# PSDT_ADC_v1_0_0.net
KiCad netlist of a schematic drawn in Altium Designer
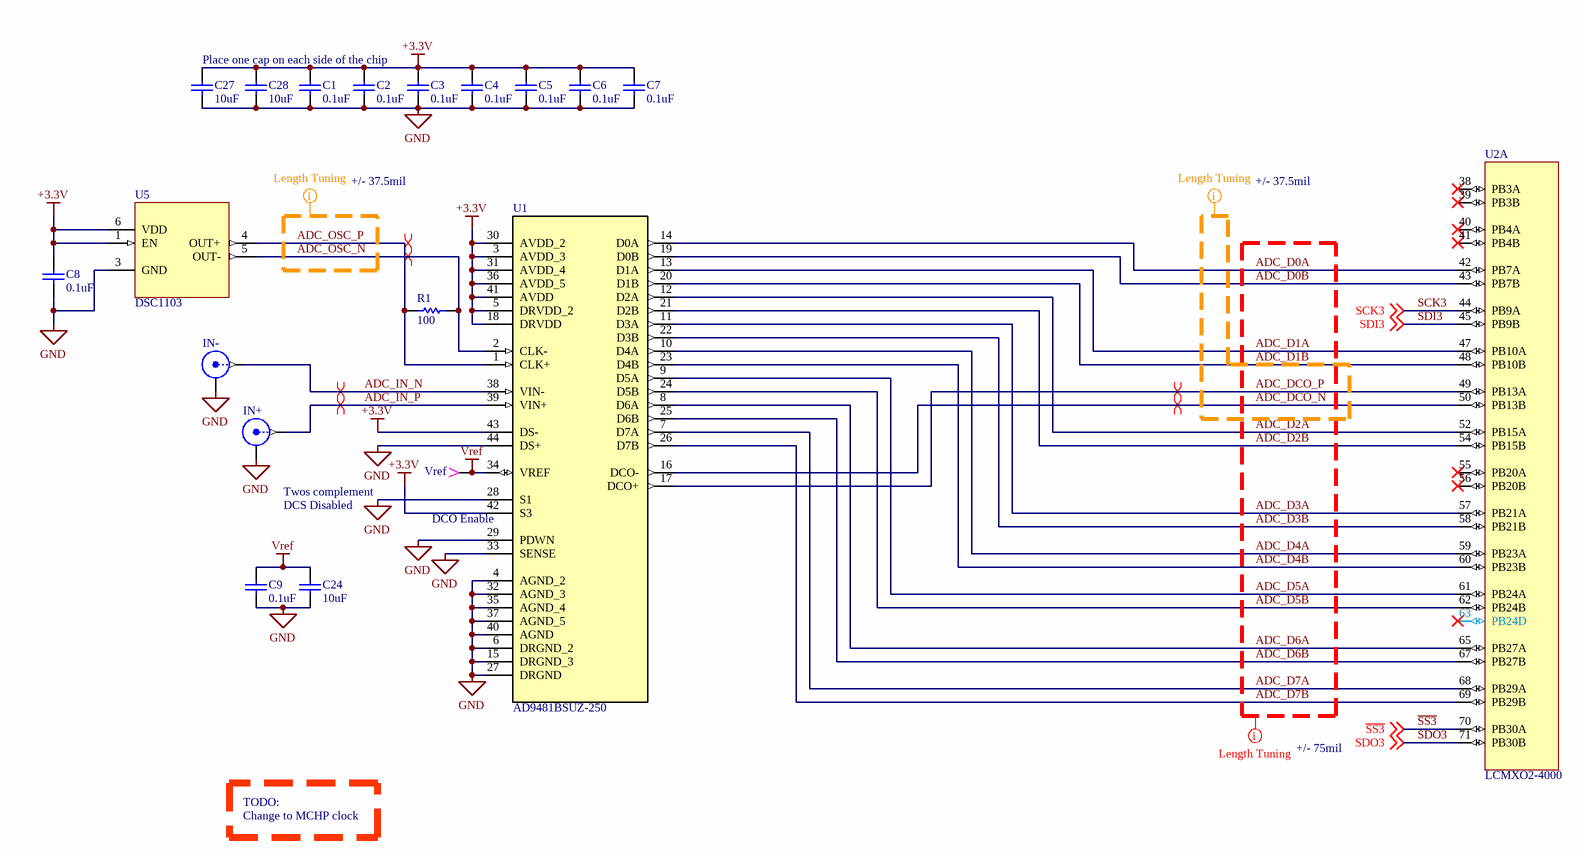
[diagram p0: PSDT ADC v1.0.0.SchDoc]

(export (version "E")
  (design (tool "Eeschema 10.0.6"))
  (components
    (comp (ref "C1")
      (value "0.1uF")
      (footprint "0402(1005)")
      (fields
        (field (name "MANF") "Samsung Electro-Mechanics")
        (field (name "TOLERANCE") "10")
        (field (name "VOLTAGE") "6.3")
        (field (name "MODIFIED BY") "jrowley")
        (field (name "APPROVED") "False")
      )
      (libsource (lib "MENG Database Library VPN") (part "Cap"))
    )
    (comp (ref "C2")
      (value "0.1uF")
      (footprint "0402(1005)")
      (fields
        (field (name "MANF") "Samsung Electro-Mechanics")
        (field (name "TOLERANCE") "10")
        (field (name "VOLTAGE") "6.3")
        (field (name "MODIFIED BY") "jrowley")
        (field (name "APPROVED") "False")
      )
      (libsource (lib "MENG Database Library VPN") (part "Cap"))
    )
    (comp (ref "C3")
      (value "0.1uF")
      (footprint "0402(1005)")
      (fields
        (field (name "MANF") "Samsung Electro-Mechanics")
        (field (name "TOLERANCE") "10")
        (field (name "VOLTAGE") "6.3")
        (field (name "MODIFIED BY") "jrowley")
        (field (name "APPROVED") "False")
      )
      (libsource (lib "MENG Database Library VPN") (part "Cap"))
    )
    (comp (ref "C4")
      (value "0.1uF")
      (footprint "0402(1005)")
      (fields
        (field (name "MANF") "Samsung Electro-Mechanics")
        (field (name "TOLERANCE") "10")
        (field (name "VOLTAGE") "6.3")
        (field (name "MODIFIED BY") "jrowley")
        (field (name "APPROVED") "False")
      )
      (libsource (lib "MENG Database Library VPN") (part "Cap"))
    )
    (comp (ref "C5")
      (value "0.1uF")
      (footprint "0402(1005)")
      (fields
        (field (name "MANF") "Samsung Electro-Mechanics")
        (field (name "TOLERANCE") "10")
        (field (name "VOLTAGE") "6.3")
        (field (name "MODIFIED BY") "jrowley")
        (field (name "APPROVED") "False")
      )
      (libsource (lib "MENG Database Library VPN") (part "Cap"))
    )
    (comp (ref "C6")
      (value "0.1uF")
      (footprint "0402(1005)")
      (fields
        (field (name "MANF") "Samsung Electro-Mechanics")
        (field (name "TOLERANCE") "10")
        (field (name "VOLTAGE") "6.3")
        (field (name "MODIFIED BY") "jrowley")
        (field (name "APPROVED") "False")
      )
      (libsource (lib "MENG Database Library VPN") (part "Cap"))
    )
    (comp (ref "C7")
      (value "0.1uF")
      (footprint "0402(1005)")
      (fields
        (field (name "MANF") "Samsung Electro-Mechanics")
        (field (name "TOLERANCE") "10")
        (field (name "VOLTAGE") "6.3")
        (field (name "MODIFIED BY") "jrowley")
        (field (name "APPROVED") "False")
      )
      (libsource (lib "MENG Database Library VPN") (part "Cap"))
    )
    (comp (ref "C8")
      (value "0.1uF")
      (footprint "0402(1005)")
      (fields
        (field (name "MANF") "Samsung Electro-Mechanics")
        (field (name "TOLERANCE") "10")
        (field (name "VOLTAGE") "6.3")
        (field (name "MODIFIED BY") "jrowley")
        (field (name "APPROVED") "False")
      )
      (libsource (lib "MENG Database Library VPN") (part "Cap"))
    )
    (comp (ref "C9")
      (value "0.1uF")
      (footprint "0402(1005)")
      (fields
        (field (name "MANF") "Samsung Electro-Mechanics")
        (field (name "TOLERANCE") "10")
        (field (name "VOLTAGE") "6.3")
        (field (name "MODIFIED BY") "jrowley")
        (field (name "APPROVED") "False")
      )
      (libsource (lib "MENG Database Library VPN") (part "Cap"))
    )
    (comp (ref "C24")
      (value "10uF")
      (footprint "0603(1608)")
      (fields
        (field (name "MANF") "Samsung Electro-Mechanics")
        (field (name "TOLERANCE") "20")
        (field (name "VOLTAGE") "25")
        (field (name "MODIFIED BY") "sotterbacher")
        (field (name "APPROVED") "True")
      )
      (libsource (lib "MENG Database Library VPN") (part "Cap"))
    )
    (comp (ref "C27")
      (value "10uF")
      (footprint "0603(1608)")
      (fields
        (field (name "MANF") "Samsung Electro-Mechanics")
        (field (name "TOLERANCE") "20")
        (field (name "VOLTAGE") "25")
        (field (name "MODIFIED BY") "sotterbacher")
        (field (name "APPROVED") "True")
      )
      (libsource (lib "MENG Database Library VPN") (part "Cap"))
    )
    (comp (ref "C28")
      (value "10uF")
      (footprint "0603(1608)")
      (fields
        (field (name "MANF") "Samsung Electro-Mechanics")
        (field (name "TOLERANCE") "20")
        (field (name "VOLTAGE") "25")
        (field (name "MODIFIED BY") "sotterbacher")
        (field (name "APPROVED") "True")
      )
      (libsource (lib "MENG Database Library VPN") (part "Cap"))
    )
    (comp (ref "IN+")
      (value "SMA")
      (footprint "TE SMA Stright")
      (fields
        (field (name "MANF") "TE Connectivity")
        (field (name "MODIFIED BY") "rlaity")
        (field (name "APPROVED") "True")
      )
      (libsource (lib "MENG Database Library VPN") (part "BNC"))
    )
    (comp (ref "IN-")
      (value "SMA")
      (footprint "TE SMA Stright")
      (fields
        (field (name "MANF") "TE Connectivity")
        (field (name "MODIFIED BY") "rlaity")
        (field (name "APPROVED") "True")
      )
      (libsource (lib "MENG Database Library VPN") (part "BNC"))
    )
    (comp (ref "R1")
      (value "100")
      (footprint "0402(1005)")
      (fields
        (field (name "MANF") "Yageo")
        (field (name "TOLERANCE") "1")
        (field (name "POWER") "0.0625")
        (field (name "MODIFIED BY") "jrowley")
        (field (name "APPROVED") "False")
      )
      (libsource (lib "MENG Database Library VPN") (part "Res1"))
    )
    (comp (ref "U1")
      (value "AD9481BSUZ-250")
      (footprint "QFP80P1200X1200X120-44N")
      (description "Single ADC Pipelined 250Msps 8-bit Parallel/LVDS 44-Pin TQFP Tray")
      (fields (field (name "MANF") "Analog Devices Inc."))
      (libsource (lib "PS") (part "AD9481BSUZ-250"))
    )
    (comp (ref "U2")
      (value "LCMXO2-4000")
      (footprint "UL_TQFP144")
      (fields (field (name "MANF") "Lattice Semiconductor Corporation"))
      (libsource (lib "PS") (part "MachXO2-4000-TG144"))
    )
    (comp (ref "U5")
      (value "DSC1103")
      (footprint "MCHP_H5A")
      (fields (field (name "MANF") "Microchip Technology"))
      (libsource (lib "PS v1.0") (part "DSC1103"))
    )
    (comp (ref "Vref")
      (value "TP")
      (footprint "TESTPOINT024")
      (fields
        (field (name "MANF") "Keystone Electronics")
        (field (name "APPROVED") "True")
        (field (name "MODIFIED BY") "sotterbacher")
      )
      (libsource (lib "MENG Database Library VPN") (part "TP"))
    )
  )
  (nets
    (net (code "1") (name "+3.3V") (class "Default")
      (node (ref "C1") (pin "2") (pinfunction "2_2") (pintype "passive"))
      (node (ref "C2") (pin "2") (pinfunction "2_2") (pintype "passive"))
      (node (ref "C27") (pin "2") (pinfunction "2_2") (pintype "passive"))
      (node (ref "C28") (pin "2") (pinfunction "2_2") (pintype "passive"))
      (node (ref "C3") (pin "2") (pinfunction "2_2") (pintype "passive"))
      (node (ref "C4") (pin "2") (pinfunction "2_2") (pintype "passive"))
      (node (ref "C5") (pin "2") (pinfunction "2_2") (pintype "passive"))
      (node (ref "C6") (pin "2") (pinfunction "2_2") (pintype "passive"))
      (node (ref "C7") (pin "2") (pinfunction "2_2") (pintype "passive"))
      (node (ref "C8") (pin "2") (pinfunction "2_2") (pintype "passive"))
      (node (ref "U1") (pin "18") (pinfunction "DRVDD_18") (pintype "power_in"))
      (node (ref "U1") (pin "3") (pinfunction "AVDD_3_3") (pintype "power_in"))
      (node (ref "U1") (pin "30") (pinfunction "AVDD_2_30") (pintype "power_in"))
      (node (ref "U1") (pin "31") (pinfunction "AVDD_4_31") (pintype "power_in"))
      (node (ref "U1") (pin "36") (pinfunction "AVDD_5_36") (pintype "power_in"))
      (node (ref "U1") (pin "41") (pinfunction "AVDD_41") (pintype "power_in"))
      (node (ref "U1") (pin "42") (pinfunction "S3_42") (pintype "passive"))
      (node (ref "U1") (pin "43") (pinfunction "DS-_43") (pintype "passive"))
      (node (ref "U1") (pin "5") (pinfunction "DRVDD_2_5") (pintype "power_in"))
      (node (ref "U5") (pin "1") (pinfunction "EN_1") (pintype "input"))
      (node (ref "U5") (pin "6") (pinfunction "VDD_6") (pintype "power_in"))
    )
    (net (code "2") (name "/ADC_D0A") (class "Default")
      (node (ref "U1") (pin "14") (pinfunction "D0A_14") (pintype "output"))
      (node (ref "U2") (pin "42") (pinfunction "PB7A_42") (pintype "bidirectional"))
    )
    (net (code "3") (name "/ADC_D0B") (class "Default")
      (node (ref "U1") (pin "19") (pinfunction "D0B_19") (pintype "output"))
      (node (ref "U2") (pin "43") (pinfunction "PB7B_43") (pintype "bidirectional"))
    )
    (net (code "4") (name "/ADC_D1A") (class "Default")
      (node (ref "U1") (pin "13") (pinfunction "D1A_13") (pintype "output"))
      (node (ref "U2") (pin "47") (pinfunction "PB10A_47") (pintype "bidirectional"))
    )
    (net (code "5") (name "/ADC_D1B") (class "Default")
      (node (ref "U1") (pin "20") (pinfunction "D1B_20") (pintype "output"))
      (node (ref "U2") (pin "48") (pinfunction "PB10B_48") (pintype "bidirectional"))
    )
    (net (code "6") (name "/ADC_D2A") (class "Default")
      (node (ref "U1") (pin "12") (pinfunction "D2A_12") (pintype "output"))
      (node (ref "U2") (pin "52") (pinfunction "PB15A_52") (pintype "bidirectional"))
    )
    (net (code "7") (name "/ADC_D2B") (class "Default")
      (node (ref "U1") (pin "21") (pinfunction "D2B_21") (pintype "output"))
      (node (ref "U2") (pin "54") (pinfunction "PB15B_54") (pintype "bidirectional"))
    )
    (net (code "8") (name "/ADC_D3A") (class "Default")
      (node (ref "U1") (pin "11") (pinfunction "D3A_11") (pintype "output"))
      (node (ref "U2") (pin "57") (pinfunction "PB21A_57") (pintype "bidirectional"))
    )
    (net (code "9") (name "/ADC_D3B") (class "Default")
      (node (ref "U1") (pin "22") (pinfunction "D3B_22") (pintype "output"))
      (node (ref "U2") (pin "58") (pinfunction "PB21B_58") (pintype "bidirectional"))
    )
    (net (code "10") (name "/ADC_D4A") (class "Default")
      (node (ref "U1") (pin "10") (pinfunction "D4A_10") (pintype "output"))
      (node (ref "U2") (pin "59") (pinfunction "PB23A_59") (pintype "bidirectional"))
    )
    (net (code "11") (name "/ADC_D4B") (class "Default")
      (node (ref "U1") (pin "23") (pinfunction "D4B_23") (pintype "output"))
      (node (ref "U2") (pin "60") (pinfunction "PB23B_60") (pintype "bidirectional"))
    )
    (net (code "12") (name "/ADC_D5A") (class "Default")
      (node (ref "U1") (pin "9") (pinfunction "D5A_9") (pintype "output"))
      (node (ref "U2") (pin "61") (pinfunction "PB24A_61") (pintype "bidirectional"))
    )
    (net (code "13") (name "/ADC_D5B") (class "Default")
      (node (ref "U1") (pin "24") (pinfunction "D5B_24") (pintype "output"))
      (node (ref "U2") (pin "62") (pinfunction "PB24B_62") (pintype "bidirectional"))
    )
    (net (code "14") (name "/ADC_D6A") (class "Default")
      (node (ref "U1") (pin "8") (pinfunction "D6A_8") (pintype "output"))
      (node (ref "U2") (pin "65") (pinfunction "PB27A_65") (pintype "bidirectional"))
    )
    (net (code "15") (name "/ADC_D6B") (class "Default")
      (node (ref "U1") (pin "25") (pinfunction "D6B_25") (pintype "output"))
      (node (ref "U2") (pin "67") (pinfunction "PB27B_67") (pintype "bidirectional"))
    )
    (net (code "16") (name "/ADC_D7A") (class "Default")
      (node (ref "U1") (pin "7") (pinfunction "D7A_7") (pintype "output"))
      (node (ref "U2") (pin "68") (pinfunction "PB29A_68") (pintype "bidirectional"))
    )
    (net (code "17") (name "/ADC_D7B") (class "Default")
      (node (ref "U1") (pin "26") (pinfunction "D7B_26") (pintype "output"))
      (node (ref "U2") (pin "69") (pinfunction "PB29B_69") (pintype "bidirectional"))
    )
    (net (code "18") (name "/ADC_DCO_N") (class "Default")
      (node (ref "U1") (pin "16") (pinfunction "DCO-_16") (pintype "output"))
      (node (ref "U2") (pin "50") (pinfunction "PB13B_50") (pintype "bidirectional"))
    )
    (net (code "19") (name "/ADC_DCO_P") (class "Default")
      (node (ref "U1") (pin "17") (pinfunction "DCO+_17") (pintype "output"))
      (node (ref "U2") (pin "49") (pinfunction "PB13A_49") (pintype "bidirectional"))
    )
    (net (code "20") (name "/ADC_IN_N") (class "Default")
      (node (ref "IN-") (pin "1") (pinfunction "X_1") (pintype "output"))
      (node (ref "U1") (pin "38") (pinfunction "VIN-_38") (pintype "input"))
    )
    (net (code "21") (name "/ADC_IN_P") (class "Default")
      (node (ref "IN+") (pin "1") (pinfunction "X_1") (pintype "output"))
      (node (ref "U1") (pin "39") (pinfunction "VIN+_39") (pintype "input"))
    )
    (net (code "22") (name "/ADC_OSC_N") (class "Default")
      (node (ref "R1") (pin "2") (pinfunction "2_2") (pintype "passive"))
      (node (ref "U1") (pin "2") (pinfunction "CLK-_2") (pintype "input"))
      (node (ref "U5") (pin "5") (pinfunction "OUT-_5") (pintype "output"))
    )
    (net (code "23") (name "/ADC_OSC_P") (class "Default")
      (node (ref "R1") (pin "1") (pinfunction "1_1") (pintype "passive"))
      (node (ref "U1") (pin "1") (pinfunction "CLK+_1") (pintype "input"))
      (node (ref "U5") (pin "4") (pinfunction "OUT+_4") (pintype "output"))
    )
    (net (code "24") (name "GND") (class "Default")
      (node (ref "C1") (pin "1") (pinfunction "1_1") (pintype "passive"))
      (node (ref "C2") (pin "1") (pinfunction "1_1") (pintype "passive"))
      (node (ref "C24") (pin "1") (pinfunction "1_1") (pintype "passive"))
      (node (ref "C27") (pin "1") (pinfunction "1_1") (pintype "passive"))
      (node (ref "C28") (pin "1") (pinfunction "1_1") (pintype "passive"))
      (node (ref "C3") (pin "1") (pinfunction "1_1") (pintype "passive"))
      (node (ref "C4") (pin "1") (pinfunction "1_1") (pintype "passive"))
      (node (ref "C5") (pin "1") (pinfunction "1_1") (pintype "passive"))
      (node (ref "C6") (pin "1") (pinfunction "1_1") (pintype "passive"))
      (node (ref "C7") (pin "1") (pinfunction "1_1") (pintype "passive"))
      (node (ref "C8") (pin "1") (pinfunction "1_1") (pintype "passive"))
      (node (ref "C9") (pin "1") (pinfunction "1_1") (pintype "passive"))
      (node (ref "IN+") (pin "2") (pinfunction "Y_2") (pintype "power_in"))
      (node (ref "IN-") (pin "2") (pinfunction "Y_2") (pintype "power_in"))
      (node (ref "U1") (pin "15") (pinfunction "DRGND_3_15") (pintype "passive"))
      (node (ref "U1") (pin "27") (pinfunction "DRGND_27") (pintype "passive"))
      (node (ref "U1") (pin "28") (pinfunction "S1_28") (pintype "passive"))
      (node (ref "U1") (pin "29") (pinfunction "PDWN_29") (pintype "passive"))
      (node (ref "U1") (pin "32") (pinfunction "AGND_3_32") (pintype "passive"))
      (node (ref "U1") (pin "33") (pinfunction "SENSE_33") (pintype "passive"))
      (node (ref "U1") (pin "35") (pinfunction "AGND_4_35") (pintype "passive"))
      (node (ref "U1") (pin "37") (pinfunction "AGND_5_37") (pintype "passive"))
      (node (ref "U1") (pin "4") (pinfunction "AGND_2_4") (pintype "passive"))
      (node (ref "U1") (pin "40") (pinfunction "AGND_40") (pintype "passive"))
      (node (ref "U1") (pin "44") (pinfunction "DS+_44") (pintype "passive"))
      (node (ref "U1") (pin "6") (pinfunction "DRGND_2_6") (pintype "passive"))
      (node (ref "U5") (pin "3") (pinfunction "GND_3") (pintype "power_in"))
    )
    (net (code "25") (name "SCK3") (class "Default")
      (node (ref "U2") (pin "44") (pinfunction "PB9A_44") (pintype "bidirectional"))
    )
    (net (code "26") (name "SDI3") (class "Default")
      (node (ref "U2") (pin "45") (pinfunction "PB9B_45") (pintype "bidirectional"))
    )
    (net (code "27") (name "SDO3") (class "Default")
      (node (ref "U2") (pin "71") (pinfunction "PB30B_71") (pintype "bidirectional"))
    )
    (net (code "28") (name "Vref") (class "Default")
      (node (ref "C24") (pin "2") (pinfunction "2_2") (pintype "passive"))
      (node (ref "C9") (pin "2") (pinfunction "2_2") (pintype "passive"))
      (node (ref "U1") (pin "34") (pinfunction "VREF_34") (pintype "bidirectional"))
      (node (ref "Vref") (pin "1") (pinfunction "1_1") (pintype "passive"))
    )
    (net (code "29") (name "unconnected-(U2A-PB3A-Pad38)") (class "Default")
      (node (ref "U2") (pin "38") (pinfunction "PB3A_38") (pintype "bidirectional+no_connect"))
    )
    (net (code "30") (name "unconnected-(U2A-PB3B-Pad39)") (class "Default")
      (node (ref "U2") (pin "39") (pinfunction "PB3B_39") (pintype "bidirectional+no_connect"))
    )
    (net (code "31") (name "unconnected-(U2A-PB4A-Pad40)") (class "Default")
      (node (ref "U2") (pin "40") (pinfunction "PB4A_40") (pintype "bidirectional+no_connect"))
    )
    (net (code "32") (name "unconnected-(U2A-PB4B-Pad41)") (class "Default")
      (node (ref "U2") (pin "41") (pinfunction "PB4B_41") (pintype "bidirectional+no_connect"))
    )
    (net (code "33") (name "unconnected-(U2A-PB20A-Pad55)") (class "Default")
      (node (ref "U2") (pin "55") (pinfunction "PB20A_55") (pintype "bidirectional+no_connect"))
    )
    (net (code "34") (name "unconnected-(U2A-PB20B-Pad56)") (class "Default")
      (node (ref "U2") (pin "56") (pinfunction "PB20B_56") (pintype "bidirectional+no_connect"))
    )
    (net (code "35") (name "unconnected-(U2A-PB24D-Pad63)") (class "Default")
      (node (ref "U2") (pin "63") (pinfunction "PB24D_63") (pintype "bidirectional+no_connect"))
    )
    (net (code "36") (name "~{SS3}") (class "Default")
      (node (ref "U2") (pin "70") (pinfunction "PB30A_70") (pintype "bidirectional"))
    )
  )
)
